# Ethernet1.net
KiCad netlist of a schematic drawn in Altium Designer
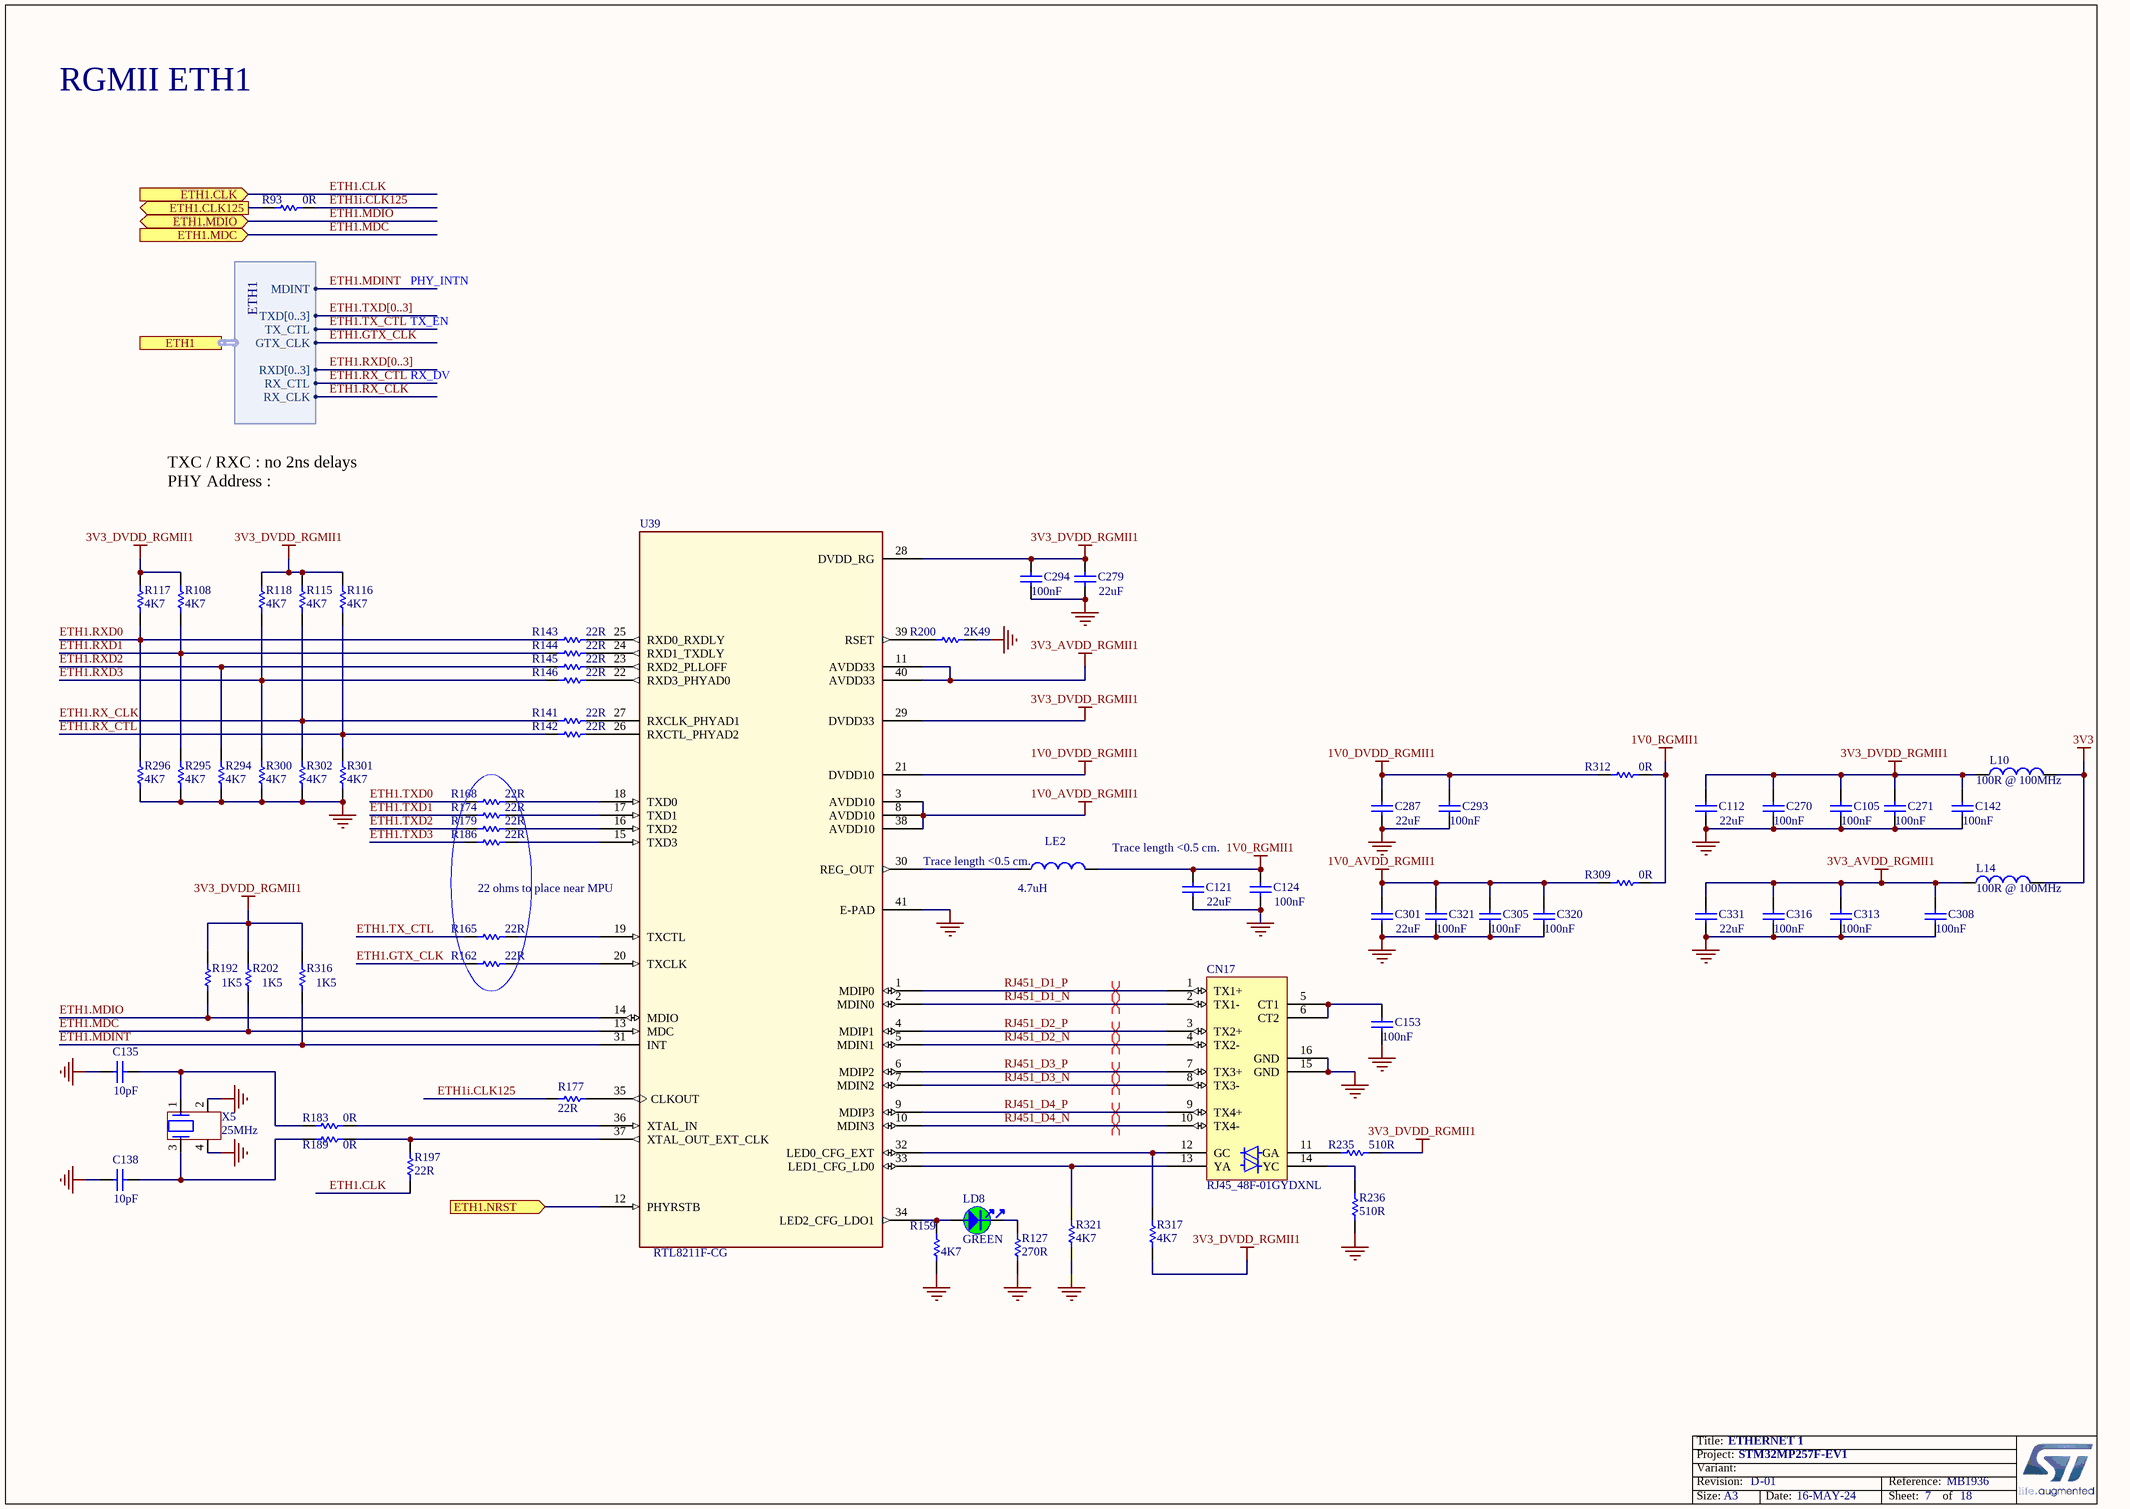
[diagram p0: Ethernet1.SchDoc]

(export (version "E")
  (design (tool "Eeschema 10.0.6"))
  (components
    (comp (ref "C105")
      (value "100nF")
      (footprint "MCD_PARTS:C0402")
      (description "Capacitor,100nF,16V,X7R,10%,0402")
      (fields
        (field (name "INTERNAL_PART_NUMBER") "MCD-00006")
        (field (name "MANUFACTURER_PART_NUMBER") "CC0402KRX7R7BB104")
        (field (name "PROVIDED_BY") "SUBCO")
      )
      (libsource (lib "MCD_PARTS_database") (part "Capacitor"))
    )
    (comp (ref "C112")
      (value "22uF")
      (footprint "MCD_PARTS:C0603")
      (description "Capacitor,22uF,6V3,X5R,20%,0603")
      (fields
        (field (name "INTERNAL_PART_NUMBER") "MCD-00100")
        (field (name "MANUFACTURER_PART_NUMBER") "GRM188R60J226MEA0J")
        (field (name "PROVIDED_BY") "SUBCO")
      )
      (libsource (lib "MCD_PARTS_database") (part "Capacitor"))
    )
    (comp (ref "C121")
      (value "22uF")
      (footprint "MCD_PARTS:C0603")
      (description "Capacitor,22uF,6V3,X5R,20%,0603")
      (fields
        (field (name "INTERNAL_PART_NUMBER") "MCD-00100")
        (field (name "MANUFACTURER_PART_NUMBER") "GRM188R60J226MEA0J")
        (field (name "PROVIDED_BY") "SUBCO")
      )
      (libsource (lib "MCD_PARTS_database") (part "Capacitor"))
    )
    (comp (ref "C124")
      (value "100nF")
      (footprint "MCD_PARTS:C0402")
      (description "Capacitor,100nF,16V,X7R,10%,0402")
      (fields
        (field (name "INTERNAL_PART_NUMBER") "MCD-00006")
        (field (name "MANUFACTURER_PART_NUMBER") "CC0402KRX7R7BB104")
        (field (name "PROVIDED_BY") "SUBCO")
      )
      (libsource (lib "MCD_PARTS_database") (part "Capacitor"))
    )
    (comp (ref "C135")
      (value "10pF")
      (footprint "MCD_PARTS:C0402")
      (description "Capacitor,10pF,50V,NPO,5%,0402")
      (fields
        (field (name "INTERNAL_PART_NUMBER") "MCD-00015")
        (field (name "MANUFACTURER_PART_NUMBER") "CC0402JRNPO9BN100")
        (field (name "PROVIDED_BY") "SUBCO")
      )
      (libsource (lib "MCD_PARTS_database") (part "Capacitor"))
    )
    (comp (ref "C138")
      (value "10pF")
      (footprint "MCD_PARTS:C0402")
      (description "Capacitor,10pF,50V,NPO,5%,0402")
      (fields
        (field (name "INTERNAL_PART_NUMBER") "MCD-00015")
        (field (name "MANUFACTURER_PART_NUMBER") "CC0402JRNPO9BN100")
        (field (name "PROVIDED_BY") "SUBCO")
      )
      (libsource (lib "MCD_PARTS_database") (part "Capacitor"))
    )
    (comp (ref "C142")
      (value "100nF")
      (footprint "MCD_PARTS:C0402")
      (description "Capacitor,100nF,16V,X7R,10%,0402")
      (fields
        (field (name "INTERNAL_PART_NUMBER") "MCD-00006")
        (field (name "MANUFACTURER_PART_NUMBER") "CC0402KRX7R7BB104")
        (field (name "PROVIDED_BY") "SUBCO")
      )
      (libsource (lib "MCD_PARTS_database") (part "Capacitor"))
    )
    (comp (ref "C153")
      (value "100nF")
      (footprint "MCD_PARTS:C0402")
      (description "Capacitor,100nF,16V,X7R,10%,0402")
      (fields
        (field (name "INTERNAL_PART_NUMBER") "MCD-00006")
        (field (name "MANUFACTURER_PART_NUMBER") "CC0402KRX7R7BB104")
        (field (name "PROVIDED_BY") "SUBCO")
      )
      (libsource (lib "MCD_PARTS_database") (part "Capacitor"))
    )
    (comp (ref "C270")
      (value "100nF")
      (footprint "MCD_PARTS:C0402")
      (description "Capacitor,100nF,16V,X7R,10%,0402")
      (fields
        (field (name "INTERNAL_PART_NUMBER") "MCD-00006")
        (field (name "MANUFACTURER_PART_NUMBER") "CC0402KRX7R7BB104")
        (field (name "PROVIDED_BY") "SUBCO")
      )
      (libsource (lib "MCD_PARTS_database") (part "Capacitor"))
    )
    (comp (ref "C271")
      (value "100nF")
      (footprint "MCD_PARTS:C0402")
      (description "Capacitor,100nF,16V,X7R,10%,0402")
      (fields
        (field (name "INTERNAL_PART_NUMBER") "MCD-00006")
        (field (name "MANUFACTURER_PART_NUMBER") "CC0402KRX7R7BB104")
        (field (name "PROVIDED_BY") "SUBCO")
      )
      (libsource (lib "MCD_PARTS_database") (part "Capacitor"))
    )
    (comp (ref "C279")
      (value "22uF")
      (footprint "MCD_PARTS:C0603")
      (description "Capacitor,22uF,6V3,X5R,20%,0603")
      (fields
        (field (name "INTERNAL_PART_NUMBER") "MCD-00100")
        (field (name "MANUFACTURER_PART_NUMBER") "GRM188R60J226MEA0J")
        (field (name "PROVIDED_BY") "SUBCO")
      )
      (libsource (lib "MCD_PARTS_database") (part "Capacitor"))
    )
    (comp (ref "C287")
      (value "22uF")
      (footprint "MCD_PARTS:C0603")
      (description "Capacitor,22uF,6V3,X5R,20%,0603")
      (fields
        (field (name "INTERNAL_PART_NUMBER") "MCD-00100")
        (field (name "MANUFACTURER_PART_NUMBER") "GRM188R60J226MEA0J")
        (field (name "PROVIDED_BY") "SUBCO")
      )
      (libsource (lib "MCD_PARTS_database") (part "Capacitor"))
    )
    (comp (ref "C293")
      (value "100nF")
      (footprint "MCD_PARTS:C0402")
      (description "Capacitor,100nF,16V,X7R,10%,0402")
      (fields
        (field (name "INTERNAL_PART_NUMBER") "MCD-00006")
        (field (name "MANUFACTURER_PART_NUMBER") "CC0402KRX7R7BB104")
        (field (name "PROVIDED_BY") "SUBCO")
      )
      (libsource (lib "MCD_PARTS_database") (part "Capacitor"))
    )
    (comp (ref "C294")
      (value "100nF")
      (footprint "MCD_PARTS:C0402")
      (description "Capacitor,100nF,16V,X7R,10%,0402")
      (fields
        (field (name "INTERNAL_PART_NUMBER") "MCD-00006")
        (field (name "MANUFACTURER_PART_NUMBER") "CC0402KRX7R7BB104")
        (field (name "PROVIDED_BY") "SUBCO")
      )
      (libsource (lib "MCD_PARTS_database") (part "Capacitor"))
    )
    (comp (ref "C301")
      (value "22uF")
      (footprint "MCD_PARTS:C0603")
      (description "Capacitor,22uF,6V3,X5R,20%,0603")
      (fields
        (field (name "INTERNAL_PART_NUMBER") "MCD-00100")
        (field (name "MANUFACTURER_PART_NUMBER") "GRM188R60J226MEA0J")
        (field (name "PROVIDED_BY") "SUBCO")
      )
      (libsource (lib "MCD_PARTS_database") (part "Capacitor"))
    )
    (comp (ref "C305")
      (value "100nF")
      (footprint "MCD_PARTS:C0402")
      (description "Capacitor,100nF,16V,X7R,10%,0402")
      (fields
        (field (name "INTERNAL_PART_NUMBER") "MCD-00006")
        (field (name "MANUFACTURER_PART_NUMBER") "CC0402KRX7R7BB104")
        (field (name "PROVIDED_BY") "SUBCO")
      )
      (libsource (lib "MCD_PARTS_database") (part "Capacitor"))
    )
    (comp (ref "C308")
      (value "100nF")
      (footprint "MCD_PARTS:C0402")
      (description "Capacitor,100nF,16V,X7R,10%,0402")
      (fields
        (field (name "INTERNAL_PART_NUMBER") "MCD-00006")
        (field (name "MANUFACTURER_PART_NUMBER") "CC0402KRX7R7BB104")
        (field (name "PROVIDED_BY") "SUBCO")
      )
      (libsource (lib "MCD_PARTS_database") (part "Capacitor"))
    )
    (comp (ref "C313")
      (value "100nF")
      (footprint "MCD_PARTS:C0402")
      (description "Capacitor,100nF,16V,X7R,10%,0402")
      (fields
        (field (name "INTERNAL_PART_NUMBER") "MCD-00006")
        (field (name "MANUFACTURER_PART_NUMBER") "CC0402KRX7R7BB104")
        (field (name "PROVIDED_BY") "SUBCO")
      )
      (libsource (lib "MCD_PARTS_database") (part "Capacitor"))
    )
    (comp (ref "C316")
      (value "100nF")
      (footprint "MCD_PARTS:C0402")
      (description "Capacitor,100nF,16V,X7R,10%,0402")
      (fields
        (field (name "INTERNAL_PART_NUMBER") "MCD-00006")
        (field (name "MANUFACTURER_PART_NUMBER") "CC0402KRX7R7BB104")
        (field (name "PROVIDED_BY") "SUBCO")
      )
      (libsource (lib "MCD_PARTS_database") (part "Capacitor"))
    )
    (comp (ref "C320")
      (value "100nF")
      (footprint "MCD_PARTS:C0402")
      (description "Capacitor,100nF,16V,X7R,10%,0402")
      (fields
        (field (name "INTERNAL_PART_NUMBER") "MCD-00006")
        (field (name "MANUFACTURER_PART_NUMBER") "CC0402KRX7R7BB104")
        (field (name "PROVIDED_BY") "SUBCO")
      )
      (libsource (lib "MCD_PARTS_database") (part "Capacitor"))
    )
    (comp (ref "C321")
      (value "100nF")
      (footprint "MCD_PARTS:C0402")
      (description "Capacitor,100nF,16V,X7R,10%,0402")
      (fields
        (field (name "INTERNAL_PART_NUMBER") "MCD-00006")
        (field (name "MANUFACTURER_PART_NUMBER") "CC0402KRX7R7BB104")
        (field (name "PROVIDED_BY") "SUBCO")
      )
      (libsource (lib "MCD_PARTS_database") (part "Capacitor"))
    )
    (comp (ref "C331")
      (value "22uF")
      (footprint "MCD_PARTS:C0603")
      (description "Capacitor,22uF,6V3,X5R,20%,0603")
      (fields
        (field (name "INTERNAL_PART_NUMBER") "MCD-00100")
        (field (name "MANUFACTURER_PART_NUMBER") "GRM188R60J226MEA0J")
        (field (name "PROVIDED_BY") "SUBCO")
      )
      (libsource (lib "MCD_PARTS_database") (part "Capacitor"))
    )
    (comp (ref "CN17")
      (value "RJ45_48F-01GYDXNL")
      (footprint "MCD_PARTS:CON_RJ45_YD_48F-01GYDXNL_LED-P")
      (description "Connector_RJ45, led pull down, T= 13.84mm")
      (fields
        (field (name "INTERNAL_PART_NUMBER") "MCD-01129")
        (field (name "MANUFACTURER_PART_NUMBER") "48F-01GYDXNL")
      )
      (libsource (lib "MCD_PARTS_database") (part "RJ45_48F_01GYDXNL_LPD"))
    )
    (comp (ref "L10")
      (value "100R @ 100MHz")
      (footprint "MCD_PARTS:FIL_0603_H0P65")
      (description "Ferrite bead 100R 2A 0603")
      (fields
        (field (name "INTERNAL_PART_NUMBER") "MCD-00094")
        (field (name "MANUFACTURER_PART_NUMBER") "BLM18EG101TN1")
        (field (name "PROVIDED_BY") "SUBCO")
      )
      (libsource (lib "MCD_PARTS_database") (part "BEAD"))
    )
    (comp (ref "L14")
      (value "100R @ 100MHz")
      (footprint "MCD_PARTS:FIL_0603_H0P65")
      (description "Ferrite bead 100R 2A 0603")
      (fields
        (field (name "INTERNAL_PART_NUMBER") "MCD-00094")
        (field (name "MANUFACTURER_PART_NUMBER") "BLM18EG101TN1")
        (field (name "PROVIDED_BY") "SUBCO")
      )
      (libsource (lib "MCD_PARTS_database") (part "BEAD"))
    )
    (comp (ref "LD8")
      (value "GREEN")
      (footprint "MCD_PARTS:LED_0603_OSRAM_LG-Q396-PS-35_GREEN_1A2K_H0P4")
      (description "LED Green, 0603 SMD, Forward Voltage Typ=2V, Max=2.5V")
      (fields
        (field (name "INTERNAL_PART_NUMBER") "MCD-00588")
        (field (name "MANUFACTURER_PART_NUMBER") "LG Q396-PS-35")
        (field (name "PROVIDED_BY") "SUBCO")
      )
      (libsource (lib "MCD_PARTS_database") (part "LED_green"))
    )
    (comp (ref "LE2")
      (value "4.7uH")
      (footprint "MCD_PARTS:L1210_LQH")
      (description "FIXED IND 4.7UH 1A 180 MOHM 30% SMD")
      (fields
        (field (name "INTERNAL_PART_NUMBER") "MCD-00048")
        (field (name "MANUFACTURER_PART_NUMBER") "LQH32PN4R7NN0L")
        (field (name "PROVIDED_BY") "SUBCO")
      )
      (libsource (lib "MCD_PARTS_database") (part "Inductor"))
    )
    (comp (ref "R93")
      (value "0R")
      (footprint "MCD_PARTS:R0402")
      (description "Resistor,0R,0402,5%,1/16W")
      (fields
        (field (name "INTERNAL_PART_NUMBER") "MCD-00052")
        (field (name "MANUFACTURER_PART_NUMBER") "RC0402JR-070RL")
        (field (name "PROVIDED_BY") "SUBCO")
      )
      (libsource (lib "MCD_PARTS_database") (part "Resistor"))
    )
    (comp (ref "R108")
      (value "4K7")
      (footprint "MCD_PARTS:R0402")
      (description "Resistor,4K7,0402,1%,1/16W")
      (fields
        (field (name "INTERNAL_PART_NUMBER") "MCD-00065")
        (field (name "MANUFACTURER_PART_NUMBER") "RC0402FR-074K7L")
        (field (name "PROVIDED_BY") "SUBCO")
      )
      (libsource (lib "MCD_PARTS_database") (part "Resistor"))
    )
    (comp (ref "R115")
      (value "4K7")
      (footprint "MCD_PARTS:R0402")
      (description "Resistor,4K7,0402,1%,1/16W")
      (fields
        (field (name "INTERNAL_PART_NUMBER") "MCD-00065")
        (field (name "MANUFACTURER_PART_NUMBER") "RC0402FR-074K7L")
        (field (name "PROVIDED_BY") "SUBCO")
      )
      (libsource (lib "MCD_PARTS_database") (part "Resistor"))
    )
    (comp (ref "R116")
      (value "4K7")
      (footprint "MCD_PARTS:R0402")
      (description "Resistor,4K7,0402,1%,1/16W")
      (fields
        (field (name "INTERNAL_PART_NUMBER") "MCD-00065")
        (field (name "MANUFACTURER_PART_NUMBER") "RC0402FR-074K7L")
        (field (name "PROVIDED_BY") "SUBCO")
      )
      (libsource (lib "MCD_PARTS_database") (part "Resistor"))
    )
    (comp (ref "R117")
      (value "4K7")
      (footprint "MCD_PARTS:R0402")
      (description "Resistor,4K7,0402,1%,1/16W")
      (fields
        (field (name "INTERNAL_PART_NUMBER") "MCD-00065")
        (field (name "MANUFACTURER_PART_NUMBER") "RC0402FR-074K7L")
        (field (name "PROVIDED_BY") "SUBCO")
      )
      (libsource (lib "MCD_PARTS_database") (part "Resistor"))
    )
    (comp (ref "R118")
      (value "4K7")
      (footprint "MCD_PARTS:R0402")
      (description "Resistor,4K7,0402,1%,1/16W")
      (fields
        (field (name "INTERNAL_PART_NUMBER") "MCD-00065")
        (field (name "MANUFACTURER_PART_NUMBER") "RC0402FR-074K7L")
        (field (name "PROVIDED_BY") "SUBCO")
      )
      (libsource (lib "MCD_PARTS_database") (part "Resistor"))
    )
    (comp (ref "R127")
      (value "270R")
      (footprint "MCD_PARTS:R0402")
      (description "Resistor,270R,0402,1%,1/16W")
      (fields
        (field (name "INTERNAL_PART_NUMBER") "MCD-00441")
        (field (name "MANUFACTURER_PART_NUMBER") "RC0402FR-07270RL")
        (field (name "PROVIDED_BY") "SUBCO")
      )
      (libsource (lib "MCD_PARTS_database") (part "Resistor"))
    )
    (comp (ref "R141")
      (value "22R")
      (footprint "MCD_PARTS:R0201_H0P23")
      (description "Resistor, 22R, 0201, +/-1%, 1/20W")
      (fields
        (field (name "INTERNAL_PART_NUMBER") "MCD-02978")
        (field (name "MANUFACTURER_PART_NUMBER") "RC0201FR-0722RL")
      )
      (libsource (lib "MCD_PARTS_database") (part "Resistor"))
    )
    (comp (ref "R142")
      (value "22R")
      (footprint "MCD_PARTS:R0201_H0P23")
      (description "Resistor, 22R, 0201, +/-1%, 1/20W")
      (fields
        (field (name "INTERNAL_PART_NUMBER") "MCD-02978")
        (field (name "MANUFACTURER_PART_NUMBER") "RC0201FR-0722RL")
      )
      (libsource (lib "MCD_PARTS_database") (part "Resistor"))
    )
    (comp (ref "R143")
      (value "22R")
      (footprint "MCD_PARTS:R0201_H0P23")
      (description "Resistor, 22R, 0201, +/-1%, 1/20W")
      (fields
        (field (name "INTERNAL_PART_NUMBER") "MCD-02978")
        (field (name "MANUFACTURER_PART_NUMBER") "RC0201FR-0722RL")
      )
      (libsource (lib "MCD_PARTS_database") (part "Resistor"))
    )
    (comp (ref "R144")
      (value "22R")
      (footprint "MCD_PARTS:R0201_H0P23")
      (description "Resistor, 22R, 0201, +/-1%, 1/20W")
      (fields
        (field (name "INTERNAL_PART_NUMBER") "MCD-02978")
        (field (name "MANUFACTURER_PART_NUMBER") "RC0201FR-0722RL")
      )
      (libsource (lib "MCD_PARTS_database") (part "Resistor"))
    )
    (comp (ref "R145")
      (value "22R")
      (footprint "MCD_PARTS:R0201_H0P23")
      (description "Resistor, 22R, 0201, +/-1%, 1/20W")
      (fields
        (field (name "INTERNAL_PART_NUMBER") "MCD-02978")
        (field (name "MANUFACTURER_PART_NUMBER") "RC0201FR-0722RL")
      )
      (libsource (lib "MCD_PARTS_database") (part "Resistor"))
    )
    (comp (ref "R146")
      (value "22R")
      (footprint "MCD_PARTS:R0201_H0P23")
      (description "Resistor, 22R, 0201, +/-1%, 1/20W")
      (fields
        (field (name "INTERNAL_PART_NUMBER") "MCD-02978")
        (field (name "MANUFACTURER_PART_NUMBER") "RC0201FR-0722RL")
      )
      (libsource (lib "MCD_PARTS_database") (part "Resistor"))
    )
    (comp (ref "R159")
      (value "4K7")
      (footprint "MCD_PARTS:R0402")
      (description "Resistor,4K7,0402,1%,1/16W")
      (fields
        (field (name "INTERNAL_PART_NUMBER") "MCD-00065")
        (field (name "MANUFACTURER_PART_NUMBER") "RC0402FR-074K7L")
        (field (name "PROVIDED_BY") "SUBCO")
      )
      (libsource (lib "MCD_PARTS_database") (part "Resistor"))
    )
    (comp (ref "R162")
      (value "22R")
      (footprint "MCD_PARTS:R0201_H0P23")
      (description "Resistor, 22R, 0201, +/-1%, 1/20W")
      (fields
        (field (name "INTERNAL_PART_NUMBER") "MCD-02978")
        (field (name "MANUFACTURER_PART_NUMBER") "RC0201FR-0722RL")
      )
      (libsource (lib "MCD_PARTS_database") (part "Resistor"))
    )
    (comp (ref "R165")
      (value "22R")
      (footprint "MCD_PARTS:R0201_H0P23")
      (description "Resistor, 22R, 0201, +/-1%, 1/20W")
      (fields
        (field (name "INTERNAL_PART_NUMBER") "MCD-02978")
        (field (name "MANUFACTURER_PART_NUMBER") "RC0201FR-0722RL")
      )
      (libsource (lib "MCD_PARTS_database") (part "Resistor"))
    )
    (comp (ref "R168")
      (value "22R")
      (footprint "MCD_PARTS:R0201_H0P23")
      (description "Resistor, 22R, 0201, +/-1%, 1/20W")
      (fields
        (field (name "INTERNAL_PART_NUMBER") "MCD-02978")
        (field (name "MANUFACTURER_PART_NUMBER") "RC0201FR-0722RL")
      )
      (libsource (lib "MCD_PARTS_database") (part "Resistor"))
    )
    (comp (ref "R174")
      (value "22R")
      (footprint "MCD_PARTS:R0201_H0P23")
      (description "Resistor, 22R, 0201, +/-1%, 1/20W")
      (fields
        (field (name "INTERNAL_PART_NUMBER") "MCD-02978")
        (field (name "MANUFACTURER_PART_NUMBER") "RC0201FR-0722RL")
      )
      (libsource (lib "MCD_PARTS_database") (part "Resistor"))
    )
    (comp (ref "R177")
      (value "22R")
      (footprint "MCD_PARTS:R0201_H0P23")
      (description "Resistor, 22R, 0201, +/-1%, 1/20W")
      (fields
        (field (name "INTERNAL_PART_NUMBER") "MCD-02978")
        (field (name "MANUFACTURER_PART_NUMBER") "RC0201FR-0722RL")
      )
      (libsource (lib "MCD_PARTS_database") (part "Resistor"))
    )
    (comp (ref "R179")
      (value "22R")
      (footprint "MCD_PARTS:R0201_H0P23")
      (description "Resistor, 22R, 0201, +/-1%, 1/20W")
      (fields
        (field (name "INTERNAL_PART_NUMBER") "MCD-02978")
        (field (name "MANUFACTURER_PART_NUMBER") "RC0201FR-0722RL")
      )
      (libsource (lib "MCD_PARTS_database") (part "Resistor"))
    )
    (comp (ref "R183")
      (value "0R")
      (footprint "MCD_PARTS:R0402")
      (description "Resistor,0R,0402,5%,1/16W")
      (fields
        (field (name "INTERNAL_PART_NUMBER") "MCD-00052")
        (field (name "MANUFACTURER_PART_NUMBER") "RC0402JR-070RL")
        (field (name "PROVIDED_BY") "SUBCO")
      )
      (libsource (lib "MCD_PARTS_database") (part "Resistor"))
    )
    (comp (ref "R186")
      (value "22R")
      (footprint "MCD_PARTS:R0201_H0P23")
      (description "Resistor, 22R, 0201, +/-1%, 1/20W")
      (fields
        (field (name "INTERNAL_PART_NUMBER") "MCD-02978")
        (field (name "MANUFACTURER_PART_NUMBER") "RC0201FR-0722RL")
      )
      (libsource (lib "MCD_PARTS_database") (part "Resistor"))
    )
    (comp (ref "R189")
      (value "0R")
      (footprint "MCD_PARTS:R0402")
      (description "Resistor,0R,0402,5%,1/16W")
      (fields
        (field (name "INTERNAL_PART_NUMBER") "MCD-00052")
        (field (name "MANUFACTURER_PART_NUMBER") "RC0402JR-070RL")
        (field (name "PROVIDED_BY") "SUBCO")
      )
      (libsource (lib "MCD_PARTS_database") (part "Resistor"))
    )
    (comp (ref "R192")
      (value "1K5")
      (footprint "MCD_PARTS:R0402")
      (description "Resistor,1K5,0402,1%,1/16W")
      (fields
        (field (name "INTERNAL_PART_NUMBER") "MCD-00068")
        (field (name "MANUFACTURER_PART_NUMBER") "RC0402FR-071K5L")
        (field (name "PROVIDED_BY") "SUBCO")
      )
      (libsource (lib "MCD_PARTS_database") (part "Resistor"))
    )
    (comp (ref "R197")
      (value "22R")
      (footprint "MCD_PARTS:R0201_H0P23")
      (description "Resistor, 22R, 0201, +/-1%, 1/20W")
      (fields
        (field (name "INTERNAL_PART_NUMBER") "MCD-02978")
        (field (name "MANUFACTURER_PART_NUMBER") "RC0201FR-0722RL")
      )
      (libsource (lib "MCD_PARTS_database") (part "Resistor"))
    )
    (comp (ref "R200")
      (value "2K49")
      (footprint "MCD_PARTS:R0402")
      (description "Resistor,2K49,0402,1%,1/16W")
      (fields
        (field (name "INTERNAL_PART_NUMBER") "MCD-00183")
        (field (name "MANUFACTURER_PART_NUMBER") "RC0402FR-072K49L")
        (field (name "PROVIDED_BY") "SUBCO")
      )
      (libsource (lib "MCD_PARTS_database") (part "Resistor"))
    )
    (comp (ref "R202")
      (value "1K5")
      (footprint "MCD_PARTS:R0402")
      (description "Resistor,1K5,0402,1%,1/16W")
      (fields
        (field (name "INTERNAL_PART_NUMBER") "MCD-00068")
        (field (name "MANUFACTURER_PART_NUMBER") "RC0402FR-071K5L")
        (field (name "PROVIDED_BY") "SUBCO")
      )
      (libsource (lib "MCD_PARTS_database") (part "Resistor"))
    )
    (comp (ref "R235")
      (value "510R")
      (footprint "MCD_PARTS:R0402")
      (description "Resistor,510R,0402,1%,1/16W")
      (fields
        (field (name "INTERNAL_PART_NUMBER") "MCD-00064")
        (field (name "MANUFACTURER_PART_NUMBER") "RC0402FR-07510RL")
        (field (name "PROVIDED_BY") "SUBCO")
      )
      (libsource (lib "MCD_PARTS_database") (part "Resistor"))
    )
    (comp (ref "R236")
      (value "510R")
      (footprint "MCD_PARTS:R0402")
      (description "Resistor,510R,0402,1%,1/16W")
      (fields
        (field (name "INTERNAL_PART_NUMBER") "MCD-00064")
        (field (name "MANUFACTURER_PART_NUMBER") "RC0402FR-07510RL")
        (field (name "PROVIDED_BY") "SUBCO")
      )
      (libsource (lib "MCD_PARTS_database") (part "Resistor"))
    )
    (comp (ref "R294")
      (value "4K7")
      (footprint "MCD_PARTS:R0402")
      (description "Resistor,4K7,0402,1%,1/16W")
      (fields
        (field (name "INTERNAL_PART_NUMBER") "MCD-00065")
        (field (name "MANUFACTURER_PART_NUMBER") "RC0402FR-074K7L")
        (field (name "PROVIDED_BY") "SUBCO")
      )
      (libsource (lib "MCD_PARTS_database") (part "Resistor"))
    )
    (comp (ref "R295")
      (value "4K7")
      (footprint "MCD_PARTS:R0402")
      (description "Resistor,4K7,0402,1%,1/16W")
      (fields
        (field (name "INTERNAL_PART_NUMBER") "MCD-00065")
        (field (name "MANUFACTURER_PART_NUMBER") "RC0402FR-074K7L")
        (field (name "PROVIDED_BY") "SUBCO")
      )
      (libsource (lib "MCD_PARTS_database") (part "Resistor"))
    )
    (comp (ref "R296")
      (value "4K7")
      (footprint "MCD_PARTS:R0402")
      (description "Resistor,4K7,0402,1%,1/16W")
      (fields
        (field (name "INTERNAL_PART_NUMBER") "MCD-00065")
        (field (name "MANUFACTURER_PART_NUMBER") "RC0402FR-074K7L")
        (field (name "PROVIDED_BY") "SUBCO")
      )
      (libsource (lib "MCD_PARTS_database") (part "Resistor"))
    )
    (comp (ref "R300")
      (value "4K7")
      (footprint "MCD_PARTS:R0402")
      (description "Resistor,4K7,0402,1%,1/16W")
      (fields
        (field (name "INTERNAL_PART_NUMBER") "MCD-00065")
        (field (name "MANUFACTURER_PART_NUMBER") "RC0402FR-074K7L")
        (field (name "PROVIDED_BY") "SUBCO")
      )
      (libsource (lib "MCD_PARTS_database") (part "Resistor"))
    )
    (comp (ref "R301")
      (value "4K7")
      (footprint "MCD_PARTS:R0402")
      (description "Resistor,4K7,0402,1%,1/16W")
      (fields
        (field (name "INTERNAL_PART_NUMBER") "MCD-00065")
        (field (name "MANUFACTURER_PART_NUMBER") "RC0402FR-074K7L")
        (field (name "PROVIDED_BY") "SUBCO")
      )
      (libsource (lib "MCD_PARTS_database") (part "Resistor"))
    )
    (comp (ref "R302")
      (value "4K7")
      (footprint "MCD_PARTS:R0402")
      (description "Resistor,4K7,0402,1%,1/16W")
      (fields
        (field (name "INTERNAL_PART_NUMBER") "MCD-00065")
        (field (name "MANUFACTURER_PART_NUMBER") "RC0402FR-074K7L")
        (field (name "PROVIDED_BY") "SUBCO")
      )
      (libsource (lib "MCD_PARTS_database") (part "Resistor"))
    )
    (comp (ref "R309")
      (value "0R")
      (footprint "MCD_PARTS:R0603")
      (description "Resistor,0R,0603,5%,1/10W")
      (fields
        (field (name "INTERNAL_PART_NUMBER") "MCD-00056")
        (field (name "MANUFACTURER_PART_NUMBER") "RC0603JR-070RL")
        (field (name "PROVIDED_BY") "SUBCO")
      )
      (libsource (lib "MCD_PARTS_database") (part "Resistor"))
    )
    (comp (ref "R312")
      (value "0R")
      (footprint "MCD_PARTS:R0603")
      (description "Resistor,0R,0603,5%,1/10W")
      (fields
        (field (name "INTERNAL_PART_NUMBER") "MCD-00056")
        (field (name "MANUFACTURER_PART_NUMBER") "RC0603JR-070RL")
        (field (name "PROVIDED_BY") "SUBCO")
      )
      (libsource (lib "MCD_PARTS_database") (part "Resistor"))
    )
    (comp (ref "R316")
      (value "1K5")
      (footprint "MCD_PARTS:R0402")
      (description "Resistor,1K5,0402,1%,1/16W")
      (fields
        (field (name "INTERNAL_PART_NUMBER") "MCD-00068")
        (field (name "MANUFACTURER_PART_NUMBER") "RC0402FR-071K5L")
        (field (name "PROVIDED_BY") "SUBCO")
      )
      (libsource (lib "MCD_PARTS_database") (part "Resistor"))
    )
    (comp (ref "R317")
      (value "4K7")
      (footprint "MCD_PARTS:R0402")
      (description "Resistor,4K7,0402,1%,1/16W")
      (fields
        (field (name "INTERNAL_PART_NUMBER") "MCD-00065")
        (field (name "MANUFACTURER_PART_NUMBER") "RC0402FR-074K7L")
        (field (name "PROVIDED_BY") "SUBCO")
      )
      (libsource (lib "MCD_PARTS_database") (part "Resistor"))
    )
    (comp (ref "R321")
      (value "4K7")
      (footprint "MCD_PARTS:R0402")
      (description "Resistor,4K7,0402,1%,1/16W")
      (fields
        (field (name "INTERNAL_PART_NUMBER") "MCD-00065")
        (field (name "MANUFACTURER_PART_NUMBER") "RC0402FR-074K7L")
        (field (name "PROVIDED_BY") "SUBCO")
      )
      (libsource (lib "MCD_PARTS_database") (part "Resistor"))
    )
    (comp (ref "U39")
      (value "RTL8211F-CG")
      (footprint "MCD_PARTS:ICC_QFN40-EPAD_5X5_P040")
      (description "10/100/1000M GIGABIT Ethernet Transceiver, QFN40 , SMPS version")
      (fields
        (field (name "INTERNAL_PART_NUMBER") "MCD-01130")
        (field (name "MANUFACTURER") "REALTEK")
        (field (name "PROVIDED_BY") "SUBCO")
      )
      (libsource (lib "MCD_PARTS_database") (part "RTL8211F-CG"))
    )
    (comp (ref "X5")
      (value "25MHz")
      (footprint "MCD_PARTS:CRY_NX3225HA_4P")
      (description "Crystal 25Mhz, 10pF, -+50PPM, SMD")
      (fields
        (field (name "INTERNAL_PART_NUMBER") "MCD-01463")
        (field (name "MANUFACTURER_PART_NUMBER") "NX3225GA-25MHZ-EXS00A-CG06750")
        (field (name "PROVIDED_BY") "SUBCO")
      )
      (libsource (lib "MCD_PARTS_database") (part "XTAL_4_PINS"))
    )
  )
  (nets
    (net (code "2") (name "/ETH1.CLK") (class "Default")
      (node (ref "R197") (pin "1") (pinfunction "1_1") (pintype "passive"))
    )
    (net (code "3") (name "/ETH1.CLK125") (class "Default")
      (node (ref "R93") (pin "1") (pinfunction "1_1") (pintype "passive"))
    )
    (net (code "4") (name "/ETH1.GTX_CLK") (class "Default")
      (node (ref "R162") (pin "1") (pinfunction "1_1") (pintype "passive"))
    )
    (net (code "5") (name "/ETH1.MDC") (class "Default")
      (node (ref "R202") (pin "1") (pinfunction "1_1") (pintype "passive"))
      (node (ref "U39") (pin "13") (pinfunction "MDC_13") (pintype "input"))
    )
    (net (code "6") (name "/ETH1.MDINT") (class "Default")
      (node (ref "R316") (pin "1") (pinfunction "1_1") (pintype "passive"))
      (node (ref "U39") (pin "31") (pinfunction "INT_31") (pintype "passive"))
    )
    (net (code "7") (name "/ETH1.MDIO") (class "Default")
      (node (ref "R192") (pin "1") (pinfunction "1_1") (pintype "passive"))
      (node (ref "U39") (pin "14") (pinfunction "MDIO_14") (pintype "bidirectional"))
    )
    (net (code "8") (name "/ETH1.NRST") (class "Default")
      (node (ref "U39") (pin "12") (pinfunction "PHYRSTB_12") (pintype "input"))
    )
    (net (code "9") (name "/ETH1.RXD0") (class "Default")
      (node (ref "R117") (pin "1") (pinfunction "1_1") (pintype "passive"))
      (node (ref "R143") (pin "1") (pinfunction "1_1") (pintype "passive"))
      (node (ref "R296") (pin "2") (pinfunction "2_2") (pintype "passive"))
    )
    (net (code "10") (name "/ETH1.RXD1") (class "Default")
      (node (ref "R108") (pin "1") (pinfunction "1_1") (pintype "passive"))
      (node (ref "R144") (pin "1") (pinfunction "1_1") (pintype "passive"))
      (node (ref "R295") (pin "2") (pinfunction "2_2") (pintype "passive"))
    )
    (net (code "11") (name "/ETH1.RXD2") (class "Default")
      (node (ref "R145") (pin "1") (pinfunction "1_1") (pintype "passive"))
      (node (ref "R294") (pin "2") (pinfunction "2_2") (pintype "passive"))
    )
    (net (code "12") (name "/ETH1.RXD3") (class "Default")
      (node (ref "R118") (pin "1") (pinfunction "1_1") (pintype "passive"))
      (node (ref "R146") (pin "1") (pinfunction "1_1") (pintype "passive"))
      (node (ref "R300") (pin "2") (pinfunction "2_2") (pintype "passive"))
    )
    (net (code "14") (name "/ETH1.RX_CLK") (class "Default")
      (node (ref "R115") (pin "1") (pinfunction "1_1") (pintype "passive"))
      (node (ref "R141") (pin "1") (pinfunction "1_1") (pintype "passive"))
      (node (ref "R302") (pin "2") (pinfunction "2_2") (pintype "passive"))
    )
    (net (code "15") (name "/ETH1.RX_CTL") (class "Default")
      (node (ref "R116") (pin "1") (pinfunction "1_1") (pintype "passive"))
      (node (ref "R142") (pin "1") (pinfunction "1_1") (pintype "passive"))
      (node (ref "R301") (pin "2") (pinfunction "2_2") (pintype "passive"))
    )
    (net (code "16") (name "/ETH1.TXD0") (class "Default")
      (node (ref "R168") (pin "1") (pinfunction "1_1") (pintype "passive"))
    )
    (net (code "17") (name "/ETH1.TXD1") (class "Default")
      (node (ref "R174") (pin "1") (pinfunction "1_1") (pintype "passive"))
    )
    (net (code "18") (name "/ETH1.TXD2") (class "Default")
      (node (ref "R179") (pin "1") (pinfunction "1_1") (pintype "passive"))
    )
    (net (code "19") (name "/ETH1.TXD3") (class "Default")
      (node (ref "R186") (pin "1") (pinfunction "1_1") (pintype "passive"))
    )
    (net (code "21") (name "/ETH1.TX_CTL") (class "Default")
      (node (ref "R165") (pin "1") (pinfunction "1_1") (pintype "passive"))
    )
    (net (code "22") (name "/ETH1i.CLK125") (class "Default")
      (node (ref "R177") (pin "1") (pinfunction "1_1") (pintype "passive"))
      (node (ref "R93") (pin "2") (pinfunction "2_2") (pintype "passive"))
    )
    (net (code "23") (name "/RJ451_D1_N") (class "Default")
      (node (ref "CN17") (pin "2") (pinfunction "TX1-_2") (pintype "bidirectional"))
      (node (ref "U39") (pin "2") (pinfunction "MDIN0_2") (pintype "bidirectional"))
    )
    (net (code "24") (name "/RJ451_D1_P") (class "Default")
      (node (ref "CN17") (pin "1") (pinfunction "TX1+_1") (pintype "bidirectional"))
      (node (ref "U39") (pin "1") (pinfunction "MDIP0_1") (pintype "bidirectional"))
    )
    (net (code "25") (name "/RJ451_D2_N") (class "Default")
      (node (ref "CN17") (pin "4") (pinfunction "TX2-_4") (pintype "bidirectional"))
      (node (ref "U39") (pin "5") (pinfunction "MDIN1_5") (pintype "bidirectional"))
    )
    (net (code "26") (name "/RJ451_D2_P") (class "Default")
      (node (ref "CN17") (pin "3") (pinfunction "TX2+_3") (pintype "bidirectional"))
      (node (ref "U39") (pin "4") (pinfunction "MDIP1_4") (pintype "bidirectional"))
    )
    (net (code "27") (name "/RJ451_D3_N") (class "Default")
      (node (ref "CN17") (pin "8") (pinfunction "TX3-_8") (pintype "bidirectional"))
      (node (ref "U39") (pin "7") (pinfunction "MDIN2_7") (pintype "bidirectional"))
    )
    (net (code "28") (name "/RJ451_D3_P") (class "Default")
      (node (ref "CN17") (pin "7") (pinfunction "TX3+_7") (pintype "bidirectional"))
      (node (ref "U39") (pin "6") (pinfunction "MDIP2_6") (pintype "bidirectional"))
    )
    (net (code "29") (name "/RJ451_D4_N") (class "Default")
      (node (ref "CN17") (pin "10") (pinfunction "TX4-_10") (pintype "bidirectional"))
      (node (ref "U39") (pin "10") (pinfunction "MDIN3_10") (pintype "bidirectional"))
    )
    (net (code "30") (name "/RJ451_D4_P") (class "Default")
      (node (ref "CN17") (pin "9") (pinfunction "TX4+_9") (pintype "bidirectional"))
      (node (ref "U39") (pin "9") (pinfunction "MDIP3_9") (pintype "bidirectional"))
    )
    (net (code "32") (name "1V0_AVDD_RGMII1") (class "Default")
      (node (ref "C301") (pin "2") (pinfunction "2_2") (pintype "passive"))
      (node (ref "C305") (pin "2") (pinfunction "2_2") (pintype "passive"))
      (node (ref "C320") (pin "2") (pinfunction "2_2") (pintype "passive"))
      (node (ref "C321") (pin "2") (pinfunction "2_2") (pintype "passive"))
      (node (ref "R309") (pin "1") (pinfunction "1_1") (pintype "passive"))
      (node (ref "U39") (pin "3") (pinfunction "AVDD10_3") (pintype "power_in"))
      (node (ref "U39") (pin "38") (pinfunction "AVDD10_38") (pintype "power_in"))
      (node (ref "U39") (pin "8") (pinfunction "AVDD10_8") (pintype "power_in"))
    )
    (net (code "33") (name "1V0_DVDD_RGMII1") (class "Default")
      (node (ref "C287") (pin "2") (pinfunction "2_2") (pintype "passive"))
      (node (ref "C293") (pin "2") (pinfunction "2_2") (pintype "passive"))
      (node (ref "R312") (pin "1") (pinfunction "1_1") (pintype "passive"))
      (node (ref "U39") (pin "21") (pinfunction "DVDD10_21") (pintype "power_in"))
    )
    (net (code "34") (name "1V0_RGMII1") (class "Default")
      (node (ref "C121") (pin "2") (pinfunction "2_2") (pintype "passive"))
      (node (ref "C124") (pin "2") (pinfunction "2_2") (pintype "passive"))
      (node (ref "LE2") (pin "2") (pinfunction "2_2") (pintype "passive"))
      (node (ref "R309") (pin "2") (pinfunction "2_2") (pintype "passive"))
      (node (ref "R312") (pin "2") (pinfunction "2_2") (pintype "passive"))
    )
    (net (code "35") (name "3V3") (class "Default")
      (node (ref "L10") (pin "2") (pinfunction "2_2") (pintype "passive"))
      (node (ref "L14") (pin "2") (pinfunction "2_2") (pintype "passive"))
    )
    (net (code "36") (name "3V3_AVDD_RGMII1") (class "Default")
      (node (ref "C308") (pin "2") (pinfunction "2_2") (pintype "passive"))
      (node (ref "C313") (pin "2") (pinfunction "2_2") (pintype "passive"))
      (node (ref "C316") (pin "2") (pinfunction "2_2") (pintype "passive"))
      (node (ref "C331") (pin "2") (pinfunction "2_2") (pintype "passive"))
      (node (ref "L14") (pin "1") (pinfunction "1_1") (pintype "passive"))
      (node (ref "U39") (pin "11") (pinfunction "AVDD33_11") (pintype "power_in"))
      (node (ref "U39") (pin "40") (pinfunction "AVDD33_40") (pintype "power_in"))
    )
    (net (code "37") (name "3V3_DVDD_RGMII1") (class "Default")
      (node (ref "C105") (pin "2") (pinfunction "2_2") (pintype "passive"))
      (node (ref "C112") (pin "2") (pinfunction "2_2") (pintype "passive"))
      (node (ref "C142") (pin "2") (pinfunction "2_2") (pintype "passive"))
      (node (ref "C270") (pin "2") (pinfunction "2_2") (pintype "passive"))
      (node (ref "C271") (pin "2") (pinfunction "2_2") (pintype "passive"))
      (node (ref "C279") (pin "1") (pinfunction "1_1") (pintype "passive"))
      (node (ref "C294") (pin "2") (pinfunction "2_2") (pintype "passive"))
      (node (ref "L10") (pin "1") (pinfunction "1_1") (pintype "passive"))
      (node (ref "R108") (pin "2") (pinfunction "2_2") (pintype "passive"))
      (node (ref "R115") (pin "2") (pinfunction "2_2") (pintype "passive"))
      (node (ref "R116") (pin "2") (pinfunction "2_2") (pintype "passive"))
      (node (ref "R117") (pin "2") (pinfunction "2_2") (pintype "passive"))
      (node (ref "R118") (pin "2") (pinfunction "2_2") (pintype "passive"))
      (node (ref "R192") (pin "2") (pinfunction "2_2") (pintype "passive"))
      (node (ref "R202") (pin "2") (pinfunction "2_2") (pintype "passive"))
      (node (ref "R235") (pin "2") (pinfunction "2_2") (pintype "passive"))
      (node (ref "R316") (pin "2") (pinfunction "2_2") (pintype "passive"))
      (node (ref "R317") (pin "1") (pinfunction "1_1") (pintype "passive"))
      (node (ref "U39") (pin "28") (pinfunction "DVDD_RG_28") (pintype "power_in"))
      (node (ref "U39") (pin "29") (pinfunction "DVDD33_29") (pintype "power_in"))
    )
    (net (code "38") (name "GND") (class "Default")
      (node (ref "C105") (pin "1") (pinfunction "1_1") (pintype "passive"))
      (node (ref "C112") (pin "1") (pinfunction "1_1") (pintype "passive"))
      (node (ref "C121") (pin "1") (pinfunction "1_1") (pintype "passive"))
      (node (ref "C124") (pin "1") (pinfunction "1_1") (pintype "passive"))
      (node (ref "C135") (pin "1") (pinfunction "1_1") (pintype "passive"))
      (node (ref "C138") (pin "1") (pinfunction "1_1") (pintype "passive"))
      (node (ref "C142") (pin "1") (pinfunction "1_1") (pintype "passive"))
      (node (ref "C153") (pin "1") (pinfunction "1_1") (pintype "passive"))
      (node (ref "C270") (pin "1") (pinfunction "1_1") (pintype "passive"))
      (node (ref "C271") (pin "1") (pinfunction "1_1") (pintype "passive"))
      (node (ref "C279") (pin "2") (pinfunction "2_2") (pintype "passive"))
      (node (ref "C287") (pin "1") (pinfunction "1_1") (pintype "passive"))
      (node (ref "C293") (pin "1") (pinfunction "1_1") (pintype "passive"))
      (node (ref "C294") (pin "1") (pinfunction "1_1") (pintype "passive"))
      (node (ref "C301") (pin "1") (pinfunction "1_1") (pintype "passive"))
      (node (ref "C305") (pin "1") (pinfunction "1_1") (pintype "passive"))
      (node (ref "C308") (pin "1") (pinfunction "1_1") (pintype "passive"))
      (node (ref "C313") (pin "1") (pinfunction "1_1") (pintype "passive"))
      (node (ref "C316") (pin "1") (pinfunction "1_1") (pintype "passive"))
      (node (ref "C320") (pin "1") (pinfunction "1_1") (pintype "passive"))
      (node (ref "C321") (pin "1") (pinfunction "1_1") (pintype "passive"))
      (node (ref "C331") (pin "1") (pinfunction "1_1") (pintype "passive"))
      (node (ref "CN17") (pin "15") (pinfunction "GND_15") (pintype "power_in"))
      (node (ref "CN17") (pin "16") (pinfunction "GND_16") (pintype "power_in"))
      (node (ref "R127") (pin "2") (pinfunction "2_2") (pintype "passive"))
      (node (ref "R159") (pin "1") (pinfunction "1_1") (pintype "passive"))
      (node (ref "R200") (pin "2") (pinfunction "2_2") (pintype "passive"))
      (node (ref "R236") (pin "1") (pinfunction "1_1") (pintype "passive"))
      (node (ref "R294") (pin "1") (pinfunction "1_1") (pintype "passive"))
      (node (ref "R295") (pin "1") (pinfunction "1_1") (pintype "passive"))
      (node (ref "R296") (pin "1") (pinfunction "1_1") (pintype "passive"))
      (node (ref "R300") (pin "1") (pinfunction "1_1") (pintype "passive"))
      (node (ref "R301") (pin "1") (pinfunction "1_1") (pintype "passive"))
      (node (ref "R302") (pin "1") (pinfunction "1_1") (pintype "passive"))
      (node (ref "R321") (pin "1") (pinfunction "1_1") (pintype "passive"))
      (node (ref "U39") (pin "41") (pinfunction "E-PAD_41") (pintype "power_in"))
      (node (ref "X5") (pin "2") (pinfunction "2_2") (pintype "passive"))
      (node (ref "X5") (pin "4") (pinfunction "4_4") (pintype "passive"))
    )
    (net (code "39") (name "Net-(C135-Pad2)") (class "Default")
      (node (ref "C135") (pin "2") (pinfunction "2_2") (pintype "passive"))
      (node (ref "R183") (pin "1") (pinfunction "1_1") (pintype "passive"))
      (node (ref "X5") (pin "1") (pinfunction "1_1") (pintype "passive"))
    )
    (net (code "40") (name "Net-(C138-Pad2)") (class "Default")
      (node (ref "C138") (pin "2") (pinfunction "2_2") (pintype "passive"))
      (node (ref "R189") (pin "1") (pinfunction "1_1") (pintype "passive"))
      (node (ref "X5") (pin "3") (pinfunction "3_3") (pintype "passive"))
    )
    (net (code "41") (name "Net-(CN17-CT1)") (class "Default")
      (node (ref "C153") (pin "2") (pinfunction "2_2") (pintype "passive"))
      (node (ref "CN17") (pin "5") (pinfunction "CT1_5") (pintype "passive"))
      (node (ref "CN17") (pin "6") (pinfunction "CT2_6") (pintype "passive"))
    )
    (net (code "42") (name "Net-(CN17-GA)") (class "Default")
      (node (ref "CN17") (pin "11") (pinfunction "GA_11") (pintype "passive"))
      (node (ref "R235") (pin "1") (pinfunction "1_1") (pintype "passive"))
    )
    (net (code "43") (name "Net-(CN17-GC)") (class "Default")
      (node (ref "CN17") (pin "12") (pinfunction "GC_12") (pintype "passive"))
      (node (ref "R317") (pin "2") (pinfunction "2_2") (pintype "passive"))
      (node (ref "U39") (pin "32") (pinfunction "LED0_CFG_EXT_32") (pintype "bidirectional"))
    )
    (net (code "44") (name "Net-(CN17-YA)") (class "Default")
      (node (ref "CN17") (pin "13") (pinfunction "YA_13") (pintype "passive"))
      (node (ref "R321") (pin "2") (pinfunction "2_2") (pintype "passive"))
      (node (ref "U39") (pin "33") (pinfunction "LED1_CFG_LD0_33") (pintype "bidirectional"))
    )
    (net (code "45") (name "Net-(CN17-YC)") (class "Default")
      (node (ref "CN17") (pin "14") (pinfunction "YC_14") (pintype "passive"))
      (node (ref "R236") (pin "2") (pinfunction "2_2") (pintype "passive"))
    )
    (net (code "46") (name "Net-(LD8-Pad2)") (class "Default")
      (node (ref "LD8") (pin "2") (pintype "passive"))
      (node (ref "R127") (pin "1") (pinfunction "1_1") (pintype "passive"))
    )
    (net (code "47") (name "Net-(U39-CLKOUT)") (class "Default")
      (node (ref "R177") (pin "2") (pinfunction "2_2") (pintype "passive"))
      (node (ref "U39") (pin "35") (pinfunction "CLKOUT_35") (pintype "output"))
    )
    (net (code "48") (name "Net-(U39-LED2_CFG_LDO1)") (class "Default")
      (node (ref "LD8") (pin "1") (pintype "passive"))
      (node (ref "R159") (pin "2") (pinfunction "2_2") (pintype "passive"))
      (node (ref "U39") (pin "34") (pinfunction "LED2_CFG_LDO1_34") (pintype "output"))
    )
    (net (code "49") (name "Net-(U39-REG_OUT)") (class "Default")
      (node (ref "LE2") (pin "1") (pinfunction "1_1") (pintype "passive"))
      (node (ref "U39") (pin "30") (pinfunction "REG_OUT_30") (pintype "output"))
    )
    (net (code "50") (name "Net-(U39-RSET)") (class "Default")
      (node (ref "R200") (pin "1") (pinfunction "1_1") (pintype "passive"))
      (node (ref "U39") (pin "39") (pinfunction "RSET_39") (pintype "output"))
    )
    (net (code "51") (name "Net-(U39-RXCLK_PHYAD1)") (class "Default")
      (node (ref "R141") (pin "2") (pinfunction "2_2") (pintype "passive"))
      (node (ref "U39") (pin "27") (pinfunction "RXCLK_PHYAD1_27") (pintype "passive"))
    )
    (net (code "52") (name "Net-(U39-RXCTL_PHYAD2)") (class "Default")
      (node (ref "R142") (pin "2") (pinfunction "2_2") (pintype "passive"))
      (node (ref "U39") (pin "26") (pinfunction "RXCTL_PHYAD2_26") (pintype "passive"))
    )
    (net (code "53") (name "Net-(U39-RXD0_RXDLY)") (class "Default")
      (node (ref "R143") (pin "2") (pinfunction "2_2") (pintype "passive"))
      (node (ref "U39") (pin "25") (pinfunction "RXD0_RXDLY_25") (pintype "output"))
    )
    (net (code "54") (name "Net-(U39-RXD1_TXDLY)") (class "Default")
      (node (ref "R144") (pin "2") (pinfunction "2_2") (pintype "passive"))
      (node (ref "U39") (pin "24") (pinfunction "RXD1_TXDLY_24") (pintype "output"))
    )
    (net (code "55") (name "Net-(U39-RXD2_PLLOFF)") (class "Default")
      (node (ref "R145") (pin "2") (pinfunction "2_2") (pintype "passive"))
      (node (ref "U39") (pin "23") (pinfunction "RXD2_PLLOFF_23") (pintype "output"))
    )
    (net (code "56") (name "Net-(U39-RXD3_PHYAD0)") (class "Default")
      (node (ref "R146") (pin "2") (pinfunction "2_2") (pintype "passive"))
      (node (ref "U39") (pin "22") (pinfunction "RXD3_PHYAD0_22") (pintype "output"))
    )
    (net (code "57") (name "Net-(U39-TXCLK)") (class "Default")
      (node (ref "R162") (pin "2") (pinfunction "2_2") (pintype "passive"))
      (node (ref "U39") (pin "20") (pinfunction "TXCLK_20") (pintype "input"))
    )
    (net (code "58") (name "Net-(U39-TXCTL)") (class "Default")
      (node (ref "R165") (pin "2") (pinfunction "2_2") (pintype "passive"))
      (node (ref "U39") (pin "19") (pinfunction "TXCTL_19") (pintype "input"))
    )
    (net (code "59") (name "Net-(U39-TXD0)") (class "Default")
      (node (ref "R168") (pin "2") (pinfunction "2_2") (pintype "passive"))
      (node (ref "U39") (pin "18") (pinfunction "TXD0_18") (pintype "input"))
    )
    (net (code "60") (name "Net-(U39-TXD1)") (class "Default")
      (node (ref "R174") (pin "2") (pinfunction "2_2") (pintype "passive"))
      (node (ref "U39") (pin "17") (pinfunction "TXD1_17") (pintype "input"))
    )
    (net (code "61") (name "Net-(U39-TXD2)") (class "Default")
      (node (ref "R179") (pin "2") (pinfunction "2_2") (pintype "passive"))
      (node (ref "U39") (pin "16") (pinfunction "TXD2_16") (pintype "input"))
    )
    (net (code "62") (name "Net-(U39-TXD3)") (class "Default")
      (node (ref "R186") (pin "2") (pinfunction "2_2") (pintype "passive"))
      (node (ref "U39") (pin "15") (pinfunction "TXD3_15") (pintype "input"))
    )
    (net (code "63") (name "Net-(U39-XTAL_IN)") (class "Default")
      (node (ref "R183") (pin "2") (pinfunction "2_2") (pintype "passive"))
      (node (ref "U39") (pin "36") (pinfunction "XTAL_IN_36") (pintype "input"))
    )
    (net (code "64") (name "Net-(U39-XTAL_OUT_EXT_CLK)") (class "Default")
      (node (ref "R189") (pin "2") (pinfunction "2_2") (pintype "passive"))
      (node (ref "R197") (pin "2") (pinfunction "2_2") (pintype "passive"))
      (node (ref "U39") (pin "37") (pinfunction "XTAL_OUT_EXT_CLK_37") (pintype "output"))
    )
  )
)
